# Main.net
KiCad netlist of a schematic drawn in Altium Designer
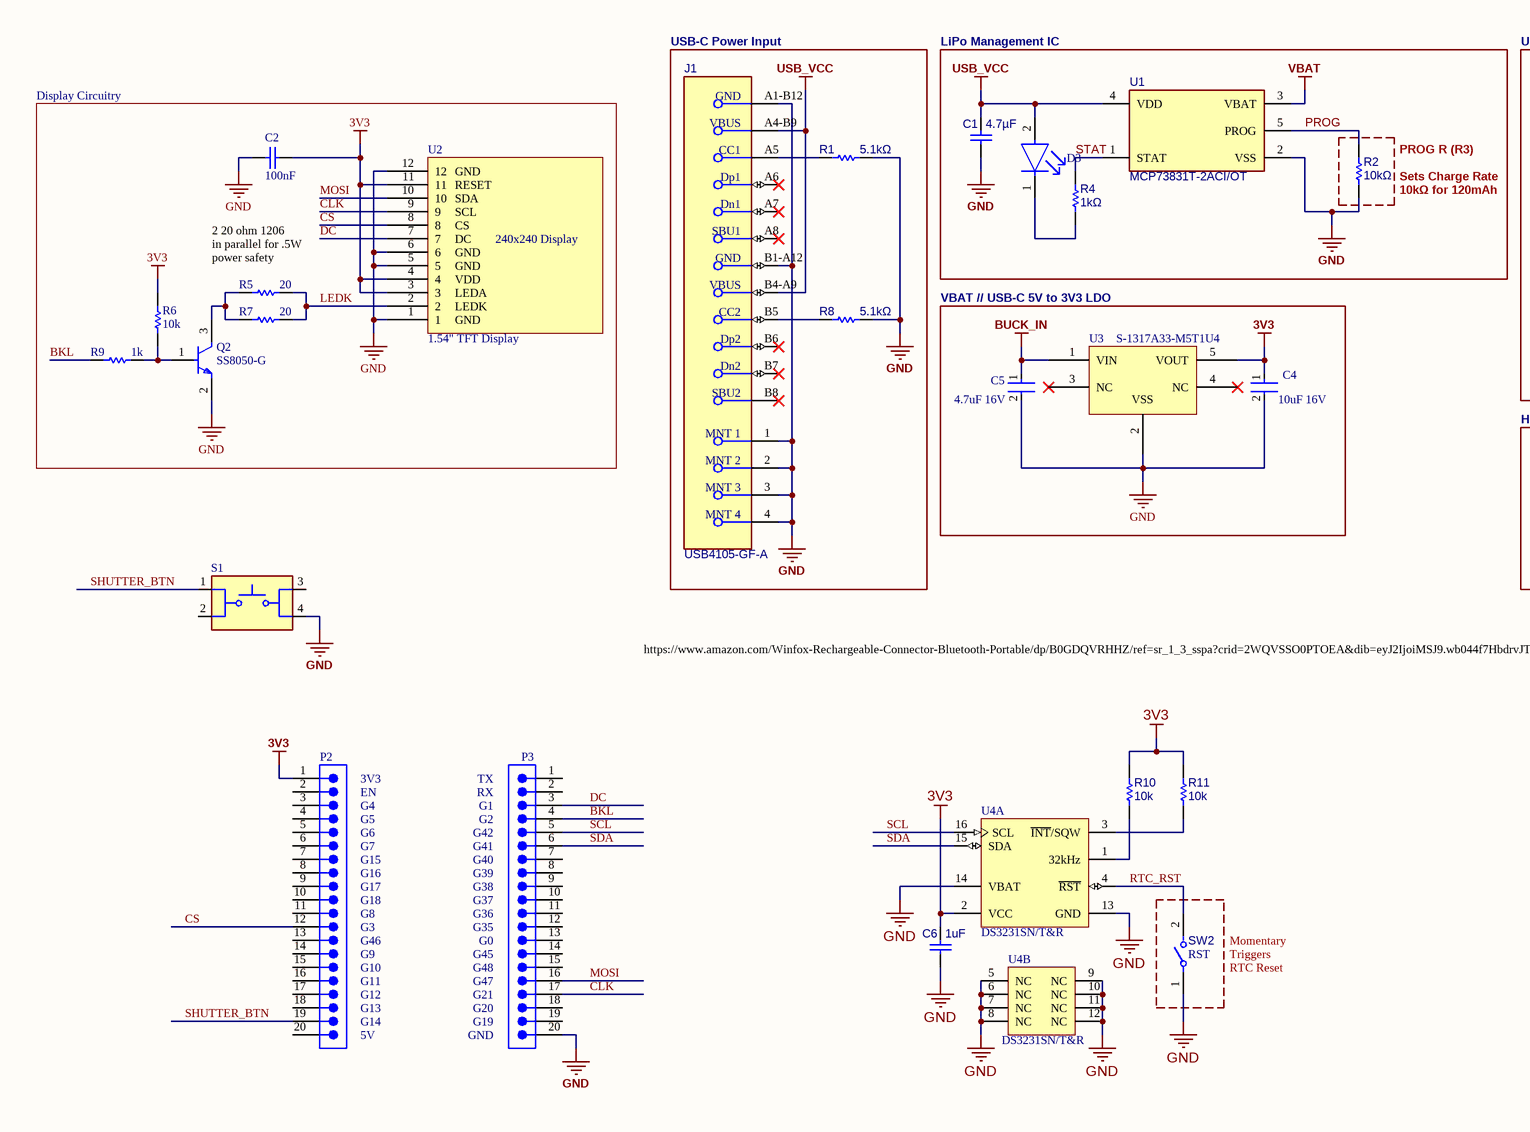
[diagram p0: Main.SchDoc, left]
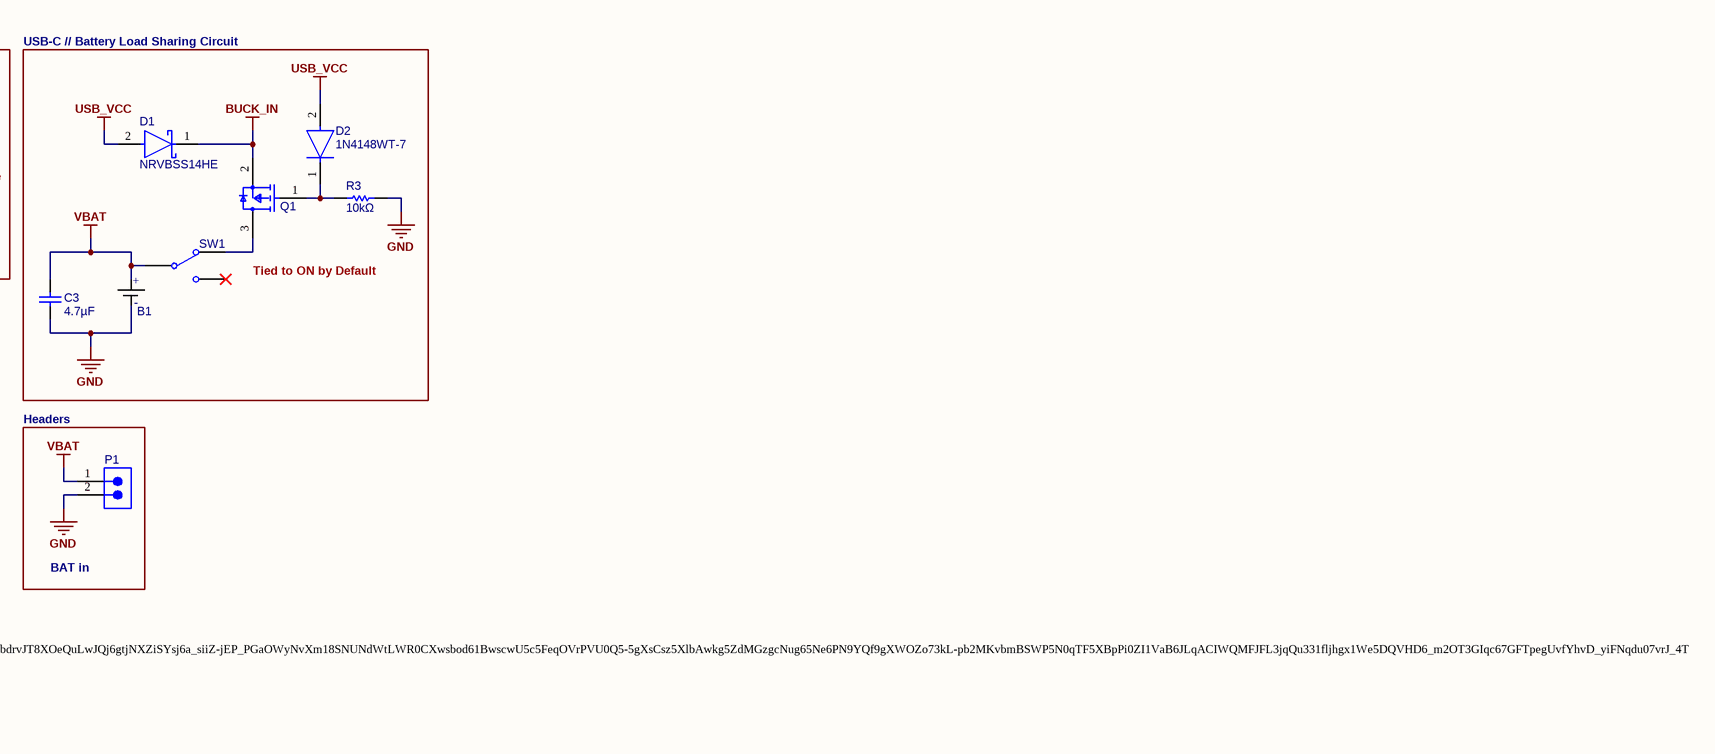
[diagram p1: Main.SchDoc, middle]
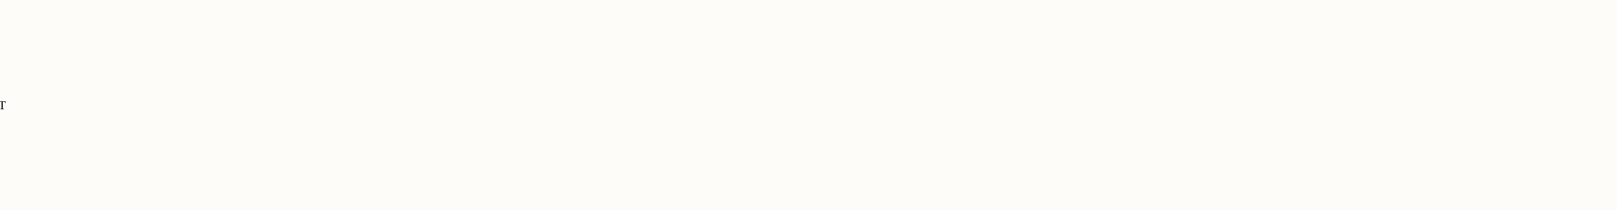
[diagram p2: Main.SchDoc, right]

(export (version "E")
  (design (tool "Eeschema 10.0.6"))
  (components
    (comp (ref "B1") (value "LiPo") (libsource (lib "LiPoSchematicLibrary") (part "3.7V 30mAh LiPo")))
    (comp (ref "C1")
      (value "4.7µF")
      (footprint "WCAP-CSGP_0603_L1.6W0.8H0.8_Reflow")
      (libsource (lib "Altium Content Vault") (part "Capacitor_Non-Polarized"))
    )
    (comp (ref "C2")
      (value "100nF")
      (footprint "CAPC1608X87X35NL15T15")
      (libsource (lib "Altium Content Vault") (part "CAP"))
    )
    (comp (ref "C3")
      (value "4.7µF")
      (footprint "WCAP-CSGP_0603_L1.6W0.8H0.8_Reflow")
      (libsource (lib "Altium Content Vault") (part "Capacitor_Non-Polarized"))
    )
    (comp (ref "C4")
      (value "10uF 16V")
      (footprint "FP-CC0603-DC-MFG")
      (description "CM105X5R106K16AT")
      (fields (field (name "TOLERANCE") "10%"))
      (libsource (lib "Altium Content Vault") (part "b4654b650e69147ec39a6b967a45e02"))
    )
    (comp (ref "C5")
      (value "4.7uF 16V")
      (footprint "FP-CC0603-DA-MFG")
      (description "GRM188Z71C475KE21D")
      (fields
        (field (name "MANUFACTURER") "YAGEO")
        (field (name "MANUFACTURER PART NUMBER") "CC0603KRX5R7BB475")
      )
      (libsource (lib "Altium Content Vault") (part "11868f565c42a9108669ba33697ecf6"))
    )
    (comp (ref "C6")
      (value "1uF")
      (footprint "WCAP-CSGP_0603_L1.6W0.8H0.8_Reflow")
      (libsource (lib "Altium Content Vault") (part "Capacitor_Non-Polarized"))
    )
    (comp (ref "D1")
      (value "NRVBSS14HE")
      (footprint "FP-477AD-MFG")
      (description "NRVBSS14HE Rectifier Diode, Schottky, 1 Phase, 1 Element, 1A, 40V V(RRM), Silicon")
      (libsource (lib "Altium Content Vault") (part "c1678fac7984e62e0809fbf79c06691"))
    )
    (comp (ref "D2")
      (value "1N4148WT-7")
      (footprint "FP-SOD523-MFG")
      (description "DIODE GEN PURP 80V 125MA SOD523")
      (libsource (lib "Altium Content Vault") (part "d7152d700b627762746794eb795d46e"))
    )
    (comp (ref "D3")
      (value "LTST-C190KGKT")
      (footprint "FP-LTST-C190KGKT-MFG")
      (description "LED GREEN CLEAR CHIP SMD")
      (libsource (lib "Altium Content Vault") (part "8706943c75ba83719d021d2fdc84c58"))
    )
    (comp (ref "J1")
      (value "USB4105-GF-A")
      (footprint "FP-USB4105-GF-A-MFG")
      (description "CONN RCPT USB2.0 TYPEC 5A")
      (fields
        (field (name "MANUFACTURER") "GCT")
        (field (name "OCTOPART") "https://octopart.com/usb4105-gf-a-gct-106627878")
      )
      (libsource (lib "Altium Content Vault") (part "e7c17a616881a82b79941196b4bec10"))
    )
    (comp (ref "P1")
      (value "61300211121")
      (footprint "61300211121")
      (libsource (lib "Altium Content Vault") (part "Header_Male_1R_02P"))
    )
    (comp (ref "P2")
      (value "61302011121")
      (footprint "61302011121")
      (description "THT Vertical Pin Header WR-PHD, Pitch 2.54 mm, Single Row, 20 pins")
      (libsource (lib "Altium Content Vault") (part "Header_Male_1R_20P"))
    )
    (comp (ref "P3")
      (value "61302011121")
      (footprint "61302011121")
      (description "THT Vertical Pin Header WR-PHD, Pitch 2.54 mm, Single Row, 20 pins")
      (libsource (lib "Altium Content Vault") (part "Header_Male_1R_20P"))
    )
    (comp (ref "Q1")
      (value "IRLML6402TRPBF")
      (footprint "FP-Micro3-MFG")
      (description "MOSFET P-CH 20V 3.7A SOT-23")
      (fields
        (field (name "OCTOPART") "https://octopart.com/irlml6402trpbf-infineon-65874989")
        (field (name "MANUFACTURER") "Infineon")
      )
      (libsource (lib "Altium Content Vault") (part "566027c8dc92b5207d53ac25ab3eb60"))
    )
    (comp (ref "Q2")
      (value "SS8050-G")
      (footprint "FP-SS8050-G-MFG")
      (description "NPN TRANSISTOR 1.5A 40V SOT-23 R")
      (libsource (lib "Altium Content Vault") (part "2a1388f82443b098dcd57d24ac7632d"))
    )
    (comp (ref "R1")
      (value "5.1kΩ")
      (footprint "RESC1608X55X25NL10T15")
      (libsource (lib "Altium Content Vault") (part "RES"))
    )
    (comp (ref "R2")
      (value "10kΩ")
      (footprint "RESC1608X55X25NL10T15")
      (libsource (lib "Altium Content Vault") (part "RES"))
    )
    (comp (ref "R3")
      (value "10kΩ")
      (footprint "RESC1608X55X25NL10T15")
      (libsource (lib "Altium Content Vault") (part "RES"))
    )
    (comp (ref "R4")
      (value "1kΩ")
      (footprint "RESC1608X55X25NL10T15")
      (libsource (lib "Altium Content Vault") (part "RES"))
    )
    (comp (ref "R5")
      (value "20")
      (footprint "RESC3116X65X40NL10T20")
      (fields (field (name "MANUFACTURER") "Yageo") (field (name "PART NUMBER") "RC1206JR-0720RL"))
      (libsource (lib "Altium Content Vault") (part "RES"))
    )
    (comp (ref "R6")
      (value "10k")
      (footprint "RESC1608X55X25NL10T15")
      (fields (field (name "PART NUMBER") "RT0603BRE071KL") (field (name "MANUFACTURER") "Yageo"))
      (libsource (lib "Altium Content Vault") (part "RES"))
    )
    (comp (ref "R7")
      (value "20")
      (footprint "RESC3116X65X40NL10T20")
      (fields (field (name "MANUFACTURER") "Yageo") (field (name "PART NUMBER") "RC1206JR-0720RL"))
      (libsource (lib "Altium Content Vault") (part "RES"))
    )
    (comp (ref "R8")
      (value "5.1kΩ")
      (footprint "RESC1608X55X25NL10T15")
      (libsource (lib "Altium Content Vault") (part "RES"))
    )
    (comp (ref "R9")
      (value "1k")
      (footprint "RESC1608X55X25NL10T15")
      (fields (field (name "PART NUMBER") "RT0603BRE071KL") (field (name "MANUFACTURER") "Yageo"))
      (libsource (lib "Altium Content Vault") (part "RES"))
    )
    (comp (ref "R10")
      (value "10k")
      (footprint "RESC1608X55X25NL10T15")
      (libsource (lib "Altium Content Vault") (part "RES"))
    )
    (comp (ref "R11")
      (value "10k")
      (footprint "RESC1608X55X25NL10T15")
      (libsource (lib "Altium Content Vault") (part "RES"))
    )
    (comp (ref "S1")
      (value "SWT0325-073016TSK_REVA")
      (footprint "SW_SWT0325-073016TSK_REVA")
      (description "6mm x 6mm Through Hole Tactile Switch")
      (fields (field (name "MF") "Global Connector Technology") (field (name "MP") "SWT0325-073016TSK"))
      (libsource (lib "SWT0325-073016TSK_REVA") (part "SWT0325-073016TSK_REVA"))
    )
    (comp (ref "SW1")
      (value "450404015514")
      (footprint "450404015514")
      (description "450404015514 Slide Switch, 0.3A, 5Vdc, Smd Rohs Compliant: Yes")
      (libsource (lib "Altium Content Vault") (part "SPDT"))
    )
    (comp (ref "SW2")
      (value "RST")
      (footprint "FP-B3U-1000P-B-MFG")
      (description "SWITCH TACTILE SPST-NO 0.05A 12V")
      (fields
        (field (name "MANUFACTURER PART NUMBER") "B3U-1000P-B")
        (field (name "OCTOPART") "https://octopart.com/b3u-1000p-b-omron-1057356")
      )
      (libsource (lib "Altium Content Vault") (part "bb27bde45df87f1f469753f287ef5ae"))
    )
    (comp (ref "U1")
      (value "MCP73831T-2ACI/OT")
      (footprint "FP-C04-091-OT-IPC_B")
      (description "IC CONTROLLR LI-ION 4.2V SOT23-5")
      (libsource (lib "Altium Content Vault") (part "61f5a3bb3429d9e0caadea342aa3b19"))
    )
    (comp (ref "U2")
      (value "1.54\" TFT Display")
      (footprint "PCBComponent_1")
      (libsource (lib "disp") (part "1.54{dblquote} TFT Display"))
    )
    (comp (ref "U3")
      (value "S-1317A33-M5T1U4")
      (footprint "S-1317A33-M5T1U4")
      (libsource (lib "1317A33-M5T1U4") (part "S-1317A33-M5T1U4"))
    )
    (comp (ref "U4")
      (value "DS3231SN/T&R")
      (footprint "W16-H2_N")
      (description "Extremely Accurate I2C-Integrated Real-Time Clock/TCXO/Crystal, 16-Pin SO, -40 to 85 degC, Reel")
      (libsource (lib "Altium Content Vault") (part "MAX-RTC-16-DS3231S-W16#H2"))
    )
  )
  (nets
    (net (code "1") (name "/BKL") (class "Default")
      (node (ref "P3") (pin "4") (pinfunction "4_4") (pintype "passive"))
      (node (ref "R9") (pin "1") (pinfunction "1_1") (pintype "passive"))
    )
    (net (code "2") (name "/CLK") (class "Default")
      (node (ref "P3") (pin "17") (pinfunction "17_17") (pintype "passive"))
      (node (ref "U2") (pin "9") (pinfunction "9_9") (pintype "passive"))
    )
    (net (code "3") (name "/CS") (class "Default")
      (node (ref "P2") (pin "12") (pinfunction "12_12") (pintype "passive"))
      (node (ref "U2") (pin "8") (pinfunction "8_8") (pintype "passive"))
    )
    (net (code "4") (name "/DC") (class "Default")
      (node (ref "P3") (pin "3") (pinfunction "3_3") (pintype "passive"))
      (node (ref "U2") (pin "7") (pinfunction "7_7") (pintype "passive"))
    )
    (net (code "5") (name "/LEDK") (class "Default")
      (node (ref "R5") (pin "2") (pinfunction "2_2") (pintype "passive"))
      (node (ref "R7") (pin "2") (pinfunction "2_2") (pintype "passive"))
      (node (ref "U2") (pin "2") (pinfunction "2_2") (pintype "passive"))
    )
    (net (code "6") (name "/MOSI") (class "Default")
      (node (ref "P3") (pin "16") (pinfunction "16_16") (pintype "passive"))
      (node (ref "U2") (pin "10") (pinfunction "10_10") (pintype "passive"))
    )
    (net (code "7") (name "/PROG") (class "Default")
      (node (ref "R2") (pin "1") (pinfunction "1_1") (pintype "passive"))
      (node (ref "U1") (pin "5") (pinfunction "PROG_5") (pintype "passive"))
    )
    (net (code "8") (name "/RTC_RST") (class "Default")
      (node (ref "SW2") (pin "2") (pinfunction "2_2") (pintype "passive"))
      (node (ref "U4") (pin "4") (pinfunction "~{RST}_4") (pintype "bidirectional"))
    )
    (net (code "9") (name "/SCL") (class "Default")
      (node (ref "P3") (pin "5") (pinfunction "5_5") (pintype "passive"))
      (node (ref "U4") (pin "16") (pinfunction "SCL_16") (pintype "input"))
    )
    (net (code "10") (name "/SDA") (class "Default")
      (node (ref "P3") (pin "6") (pinfunction "6_6") (pintype "passive"))
      (node (ref "U4") (pin "15") (pinfunction "SDA_15") (pintype "bidirectional"))
    )
    (net (code "11") (name "/SHUTTER_BTN") (class "Default")
      (node (ref "P2") (pin "19") (pinfunction "19_19") (pintype "passive"))
      (node (ref "S1") (pin "1") (pinfunction "1_1") (pintype "passive"))
    )
    (net (code "12") (name "/STAT") (class "Default")
      (node (ref "R4") (pin "2") (pinfunction "2_2") (pintype "passive"))
      (node (ref "U1") (pin "1") (pinfunction "STAT_1") (pintype "passive"))
    )
    (net (code "13") (name "3V3") (class "Default")
      (node (ref "C2") (pin "1") (pinfunction "1_1") (pintype "passive"))
      (node (ref "C4") (pin "1") (pinfunction "1_1") (pintype "passive"))
      (node (ref "C6") (pin "2") (pinfunction "2_2") (pintype "passive"))
      (node (ref "P2") (pin "1") (pinfunction "1_1") (pintype "passive"))
      (node (ref "R10") (pin "1") (pinfunction "1_1") (pintype "passive"))
      (node (ref "R11") (pin "1") (pinfunction "1_1") (pintype "passive"))
      (node (ref "R6") (pin "2") (pinfunction "2_2") (pintype "passive"))
      (node (ref "U2") (pin "11") (pinfunction "11_11") (pintype "passive"))
      (node (ref "U2") (pin "3") (pinfunction "3_3") (pintype "passive"))
      (node (ref "U2") (pin "4") (pinfunction "4_4") (pintype "passive"))
      (node (ref "U3") (pin "5") (pinfunction "VOUT_5") (pintype "passive"))
      (node (ref "U4") (pin "2") (pinfunction "VCC_2") (pintype "power_in"))
    )
    (net (code "14") (name "BUCK_IN") (class "Default")
      (node (ref "C5") (pin "1") (pinfunction "1_1") (pintype "passive"))
      (node (ref "D1") (pin "1") (pinfunction "C_1") (pintype "passive"))
      (node (ref "Q1") (pin "2") (pinfunction "S_2") (pintype "passive"))
      (node (ref "U3") (pin "1") (pinfunction "VIN_1") (pintype "passive"))
    )
    (net (code "15") (name "GND") (class "Default")
      (node (ref "B1") (pin "1") (pinfunction "-_1") (pintype "passive"))
      (node (ref "C1") (pin "1") (pinfunction "1_1") (pintype "passive"))
      (node (ref "C2") (pin "2") (pinfunction "2_2") (pintype "passive"))
      (node (ref "C3") (pin "1") (pinfunction "1_1") (pintype "passive"))
      (node (ref "C4") (pin "2") (pinfunction "2_2") (pintype "passive"))
      (node (ref "C5") (pin "2") (pinfunction "2_2") (pintype "passive"))
      (node (ref "C6") (pin "1") (pinfunction "1_1") (pintype "passive"))
      (node (ref "J1") (pin "1") (pinfunction "MNT_1_1") (pintype "power_in"))
      (node (ref "J1") (pin "2") (pinfunction "MNT_2_2") (pintype "power_in"))
      (node (ref "J1") (pin "3") (pinfunction "MNT_3_3") (pintype "power_in"))
      (node (ref "J1") (pin "4") (pinfunction "MNT_4_4") (pintype "power_in"))
      (node (ref "J1") (pin "A1-B12") (pinfunction "GND_A1-B12") (pintype "power_in"))
      (node (ref "J1") (pin "B1-A12") (pinfunction "GND_B1-A12") (pintype "bidirectional"))
      (node (ref "P1") (pin "2") (pinfunction "2_2") (pintype "passive"))
      (node (ref "P3") (pin "20") (pinfunction "20_20") (pintype "passive"))
      (node (ref "Q2") (pin "2") (pinfunction "E_2") (pintype "passive"))
      (node (ref "R1") (pin "1") (pinfunction "1_1") (pintype "passive"))
      (node (ref "R2") (pin "2") (pinfunction "2_2") (pintype "passive"))
      (node (ref "R3") (pin "2") (pinfunction "2_2") (pintype "passive"))
      (node (ref "R8") (pin "1") (pinfunction "1_1") (pintype "passive"))
      (node (ref "S1") (pin "4") (pinfunction "4_4") (pintype "passive"))
      (node (ref "SW2") (pin "1") (pinfunction "1_1") (pintype "passive"))
      (node (ref "U1") (pin "2") (pinfunction "VSS_2") (pintype "power_in"))
      (node (ref "U2") (pin "1") (pinfunction "1_1") (pintype "passive"))
      (node (ref "U2") (pin "12") (pinfunction "12_12") (pintype "passive"))
      (node (ref "U2") (pin "5") (pinfunction "5_5") (pintype "passive"))
      (node (ref "U2") (pin "6") (pinfunction "6_6") (pintype "passive"))
      (node (ref "U3") (pin "2") (pinfunction "VSS_2") (pintype "passive"))
      (node (ref "U4") (pin "10") (pinfunction "NC_10") (pintype "passive"))
      (node (ref "U4") (pin "11") (pinfunction "NC_11") (pintype "passive"))
      (node (ref "U4") (pin "12") (pinfunction "NC_12") (pintype "passive"))
      (node (ref "U4") (pin "13") (pinfunction "GND_13") (pintype "power_in"))
      (node (ref "U4") (pin "14") (pinfunction "VBAT_14") (pintype "power_in"))
      (node (ref "U4") (pin "5") (pinfunction "NC_5") (pintype "passive"))
      (node (ref "U4") (pin "6") (pinfunction "NC_6") (pintype "passive"))
      (node (ref "U4") (pin "7") (pinfunction "NC_7") (pintype "passive"))
      (node (ref "U4") (pin "8") (pinfunction "NC_8") (pintype "passive"))
      (node (ref "U4") (pin "9") (pinfunction "NC_9") (pintype "passive"))
    )
    (net (code "16") (name "Net-(D2-C)") (class "Default")
      (node (ref "D2") (pin "1") (pinfunction "C_1") (pintype "passive"))
      (node (ref "Q1") (pin "1") (pinfunction "G_1") (pintype "passive"))
      (node (ref "R3") (pin "1") (pinfunction "1_1") (pintype "passive"))
    )
    (net (code "17") (name "Net-(D3-C)") (class "Default")
      (node (ref "D3") (pin "1") (pinfunction "C_1") (pintype "passive"))
      (node (ref "R4") (pin "1") (pinfunction "1_1") (pintype "passive"))
    )
    (net (code "18") (name "Net-(J1-CC1)") (class "Default")
      (node (ref "J1") (pin "A5") (pinfunction "CC1_A5") (pintype "power_in"))
      (node (ref "R1") (pin "2") (pinfunction "2_2") (pintype "passive"))
    )
    (net (code "19") (name "Net-(J1-CC2)") (class "Default")
      (node (ref "J1") (pin "B5") (pinfunction "CC2_B5") (pintype "bidirectional"))
      (node (ref "R8") (pin "2") (pinfunction "2_2") (pintype "passive"))
    )
    (net (code "20") (name "Net-(Q1-D)") (class "Default")
      (node (ref "Q1") (pin "3") (pinfunction "D_3") (pintype "passive"))
      (node (ref "SW1") (pin "L1") (pinfunction "L1_L1") (pintype "passive"))
    )
    (net (code "21") (name "Net-(Q2-B)") (class "Default")
      (node (ref "Q2") (pin "1") (pinfunction "B_1") (pintype "passive"))
      (node (ref "R6") (pin "1") (pinfunction "1_1") (pintype "passive"))
      (node (ref "R9") (pin "2") (pinfunction "2_2") (pintype "passive"))
    )
    (net (code "22") (name "Net-(Q2-C)") (class "Default")
      (node (ref "Q2") (pin "3") (pinfunction "C_3") (pintype "passive"))
      (node (ref "R5") (pin "1") (pinfunction "1_1") (pintype "passive"))
      (node (ref "R7") (pin "1") (pinfunction "1_1") (pintype "passive"))
    )
    (net (code "23") (name "Net-(U4A-32kHz)") (class "Default")
      (node (ref "R10") (pin "2") (pinfunction "2_2") (pintype "passive"))
      (node (ref "U4") (pin "1") (pinfunction "32kHz_1") (pintype "open_collector"))
    )
    (net (code "24") (name "Net-(U4A-~{INT}{slash}SQW)") (class "Default")
      (node (ref "R11") (pin "2") (pinfunction "2_2") (pintype "passive"))
      (node (ref "U4") (pin "3") (pinfunction "~{INT}/SQW_3") (pintype "open_collector"))
    )
    (net (code "25") (name "USB_VCC") (class "Default")
      (node (ref "C1") (pin "2") (pinfunction "2_2") (pintype "passive"))
      (node (ref "D1") (pin "2") (pinfunction "A_2") (pintype "passive"))
      (node (ref "D2") (pin "2") (pinfunction "A_2") (pintype "passive"))
      (node (ref "D3") (pin "2") (pinfunction "A_2") (pintype "passive"))
      (node (ref "J1") (pin "A4-B9") (pinfunction "VBUS_A4-B9") (pintype "power_in"))
      (node (ref "J1") (pin "B4-A9") (pinfunction "VBUS_B4-A9") (pintype "bidirectional"))
      (node (ref "U1") (pin "4") (pinfunction "VDD_4") (pintype "power_in"))
    )
    (net (code "26") (name "VBAT") (class "Default")
      (node (ref "B1") (pin "0") (pinfunction "+_0") (pintype "passive"))
      (node (ref "C3") (pin "2") (pinfunction "2_2") (pintype "passive"))
      (node (ref "P1") (pin "1") (pinfunction "1_1") (pintype "passive"))
      (node (ref "SW1") (pin "COM") (pinfunction "COM_COM") (pintype "passive"))
      (node (ref "U1") (pin "3") (pinfunction "VBAT_3") (pintype "power_in"))
    )
    (net (code "27") (name "unconnected-(J1-Dn1-PadA7)") (class "Default")
      (node (ref "J1") (pin "A7") (pinfunction "Dn1_A7") (pintype "bidirectional+no_connect"))
    )
    (net (code "28") (name "unconnected-(J1-Dn2-PadB7)") (class "Default")
      (node (ref "J1") (pin "B7") (pinfunction "Dn2_B7") (pintype "bidirectional+no_connect"))
    )
    (net (code "29") (name "unconnected-(J1-Dp1-PadA6)") (class "Default")
      (node (ref "J1") (pin "A6") (pinfunction "Dp1_A6") (pintype "bidirectional+no_connect"))
    )
    (net (code "30") (name "unconnected-(J1-Dp2-PadB6)") (class "Default")
      (node (ref "J1") (pin "B6") (pinfunction "Dp2_B6") (pintype "bidirectional+no_connect"))
    )
    (net (code "31") (name "unconnected-(J1-SBU1-PadA8)") (class "Default")
      (node (ref "J1") (pin "A8") (pinfunction "SBU1_A8") (pintype "bidirectional+no_connect"))
    )
    (net (code "32") (name "unconnected-(J1-SBU2-PadB8)") (class "Default")
      (node (ref "J1") (pin "B8") (pinfunction "SBU2_B8") (pintype "power_in+no_connect"))
    )
    (net (code "33") (name "unconnected-(P2-Pad2)") (class "Default")
      (node (ref "P2") (pin "2") (pinfunction "2_2") (pintype "passive"))
    )
    (net (code "34") (name "unconnected-(P2-Pad3)") (class "Default")
      (node (ref "P2") (pin "3") (pinfunction "3_3") (pintype "passive"))
    )
    (net (code "35") (name "unconnected-(P2-Pad4)") (class "Default")
      (node (ref "P2") (pin "4") (pinfunction "4_4") (pintype "passive"))
    )
    (net (code "36") (name "unconnected-(P2-Pad5)") (class "Default")
      (node (ref "P2") (pin "5") (pinfunction "5_5") (pintype "passive"))
    )
    (net (code "37") (name "unconnected-(P2-Pad6)") (class "Default")
      (node (ref "P2") (pin "6") (pinfunction "6_6") (pintype "passive"))
    )
    (net (code "38") (name "unconnected-(P2-Pad7)") (class "Default")
      (node (ref "P2") (pin "7") (pinfunction "7_7") (pintype "passive"))
    )
    (net (code "39") (name "unconnected-(P2-Pad8)") (class "Default")
      (node (ref "P2") (pin "8") (pinfunction "8_8") (pintype "passive"))
    )
    (net (code "40") (name "unconnected-(P2-Pad9)") (class "Default")
      (node (ref "P2") (pin "9") (pinfunction "9_9") (pintype "passive"))
    )
    (net (code "41") (name "unconnected-(P2-Pad10)") (class "Default")
      (node (ref "P2") (pin "10") (pinfunction "10_10") (pintype "passive"))
    )
    (net (code "42") (name "unconnected-(P2-Pad11)") (class "Default")
      (node (ref "P2") (pin "11") (pinfunction "11_11") (pintype "passive"))
    )
    (net (code "43") (name "unconnected-(P2-Pad13)") (class "Default")
      (node (ref "P2") (pin "13") (pinfunction "13_13") (pintype "passive"))
    )
    (net (code "44") (name "unconnected-(P2-Pad14)") (class "Default")
      (node (ref "P2") (pin "14") (pinfunction "14_14") (pintype "passive"))
    )
    (net (code "45") (name "unconnected-(P2-Pad15)") (class "Default")
      (node (ref "P2") (pin "15") (pinfunction "15_15") (pintype "passive"))
    )
    (net (code "46") (name "unconnected-(P2-Pad16)") (class "Default")
      (node (ref "P2") (pin "16") (pinfunction "16_16") (pintype "passive"))
    )
    (net (code "47") (name "unconnected-(P2-Pad17)") (class "Default")
      (node (ref "P2") (pin "17") (pinfunction "17_17") (pintype "passive"))
    )
    (net (code "48") (name "unconnected-(P2-Pad18)") (class "Default")
      (node (ref "P2") (pin "18") (pinfunction "18_18") (pintype "passive"))
    )
    (net (code "49") (name "unconnected-(P2-Pad20)") (class "Default")
      (node (ref "P2") (pin "20") (pinfunction "20_20") (pintype "passive"))
    )
    (net (code "50") (name "unconnected-(P3-Pad1)") (class "Default")
      (node (ref "P3") (pin "1") (pinfunction "1_1") (pintype "passive"))
    )
    (net (code "51") (name "unconnected-(P3-Pad2)") (class "Default")
      (node (ref "P3") (pin "2") (pinfunction "2_2") (pintype "passive"))
    )
    (net (code "52") (name "unconnected-(P3-Pad7)") (class "Default")
      (node (ref "P3") (pin "7") (pinfunction "7_7") (pintype "passive"))
    )
    (net (code "53") (name "unconnected-(P3-Pad8)") (class "Default")
      (node (ref "P3") (pin "8") (pinfunction "8_8") (pintype "passive"))
    )
    (net (code "54") (name "unconnected-(P3-Pad9)") (class "Default")
      (node (ref "P3") (pin "9") (pinfunction "9_9") (pintype "passive"))
    )
    (net (code "55") (name "unconnected-(P3-Pad10)") (class "Default")
      (node (ref "P3") (pin "10") (pinfunction "10_10") (pintype "passive"))
    )
    (net (code "56") (name "unconnected-(P3-Pad11)") (class "Default")
      (node (ref "P3") (pin "11") (pinfunction "11_11") (pintype "passive"))
    )
    (net (code "57") (name "unconnected-(P3-Pad12)") (class "Default")
      (node (ref "P3") (pin "12") (pinfunction "12_12") (pintype "passive"))
    )
    (net (code "58") (name "unconnected-(P3-Pad13)") (class "Default")
      (node (ref "P3") (pin "13") (pinfunction "13_13") (pintype "passive"))
    )
    (net (code "59") (name "unconnected-(P3-Pad14)") (class "Default")
      (node (ref "P3") (pin "14") (pinfunction "14_14") (pintype "passive"))
    )
    (net (code "60") (name "unconnected-(P3-Pad15)") (class "Default")
      (node (ref "P3") (pin "15") (pinfunction "15_15") (pintype "passive"))
    )
    (net (code "61") (name "unconnected-(P3-Pad18)") (class "Default")
      (node (ref "P3") (pin "18") (pinfunction "18_18") (pintype "passive"))
    )
    (net (code "62") (name "unconnected-(P3-Pad19)") (class "Default")
      (node (ref "P3") (pin "19") (pinfunction "19_19") (pintype "passive"))
    )
    (net (code "63") (name "unconnected-(S1-Pad2)") (class "Default")
      (node (ref "S1") (pin "2") (pinfunction "2_2") (pintype "passive"))
    )
    (net (code "64") (name "unconnected-(S1-Pad3)") (class "Default")
      (node (ref "S1") (pin "3") (pinfunction "3_3") (pintype "passive"))
    )
    (net (code "65") (name "unconnected-(SW1-PadL2)") (class "Default")
      (node (ref "SW1") (pin "L2") (pinfunction "L2_L2") (pintype "passive+no_connect"))
    )
    (net (code "66") (name "unconnected-(U3-NC-Pad3)") (class "Default")
      (node (ref "U3") (pin "3") (pinfunction "NC_3") (pintype "passive+no_connect"))
    )
    (net (code "67") (name "unconnected-(U3-NC-Pad4)") (class "Default")
      (node (ref "U3") (pin "4") (pinfunction "NC_4") (pintype "passive+no_connect"))
    )
  )
)
